# iognd.net
KiCad netlist of a schematic drawn in EAGLE
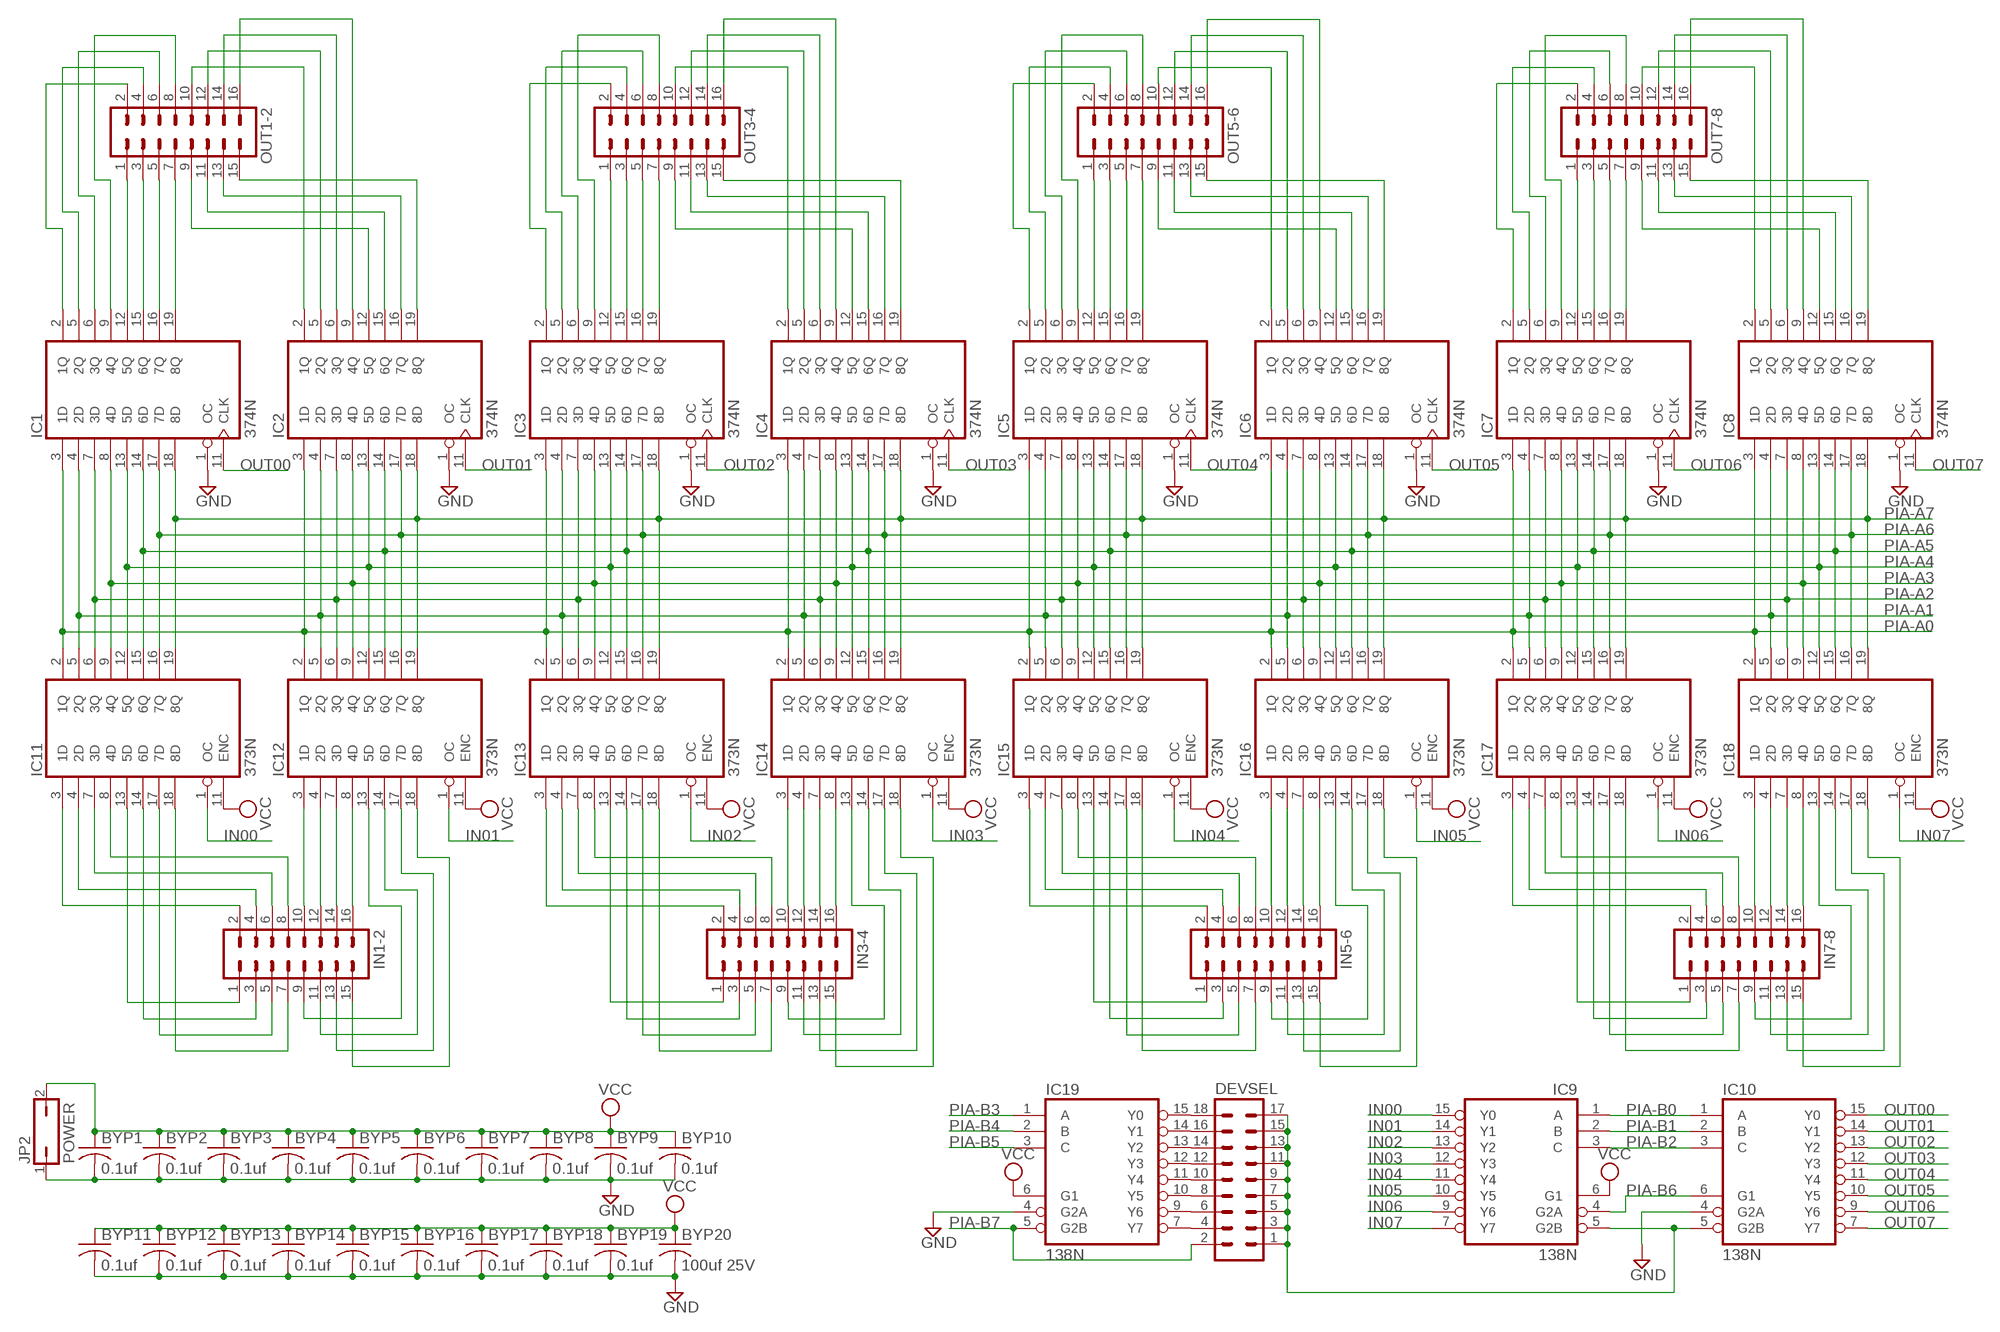
[diagram p0: schematic, sheet 1]
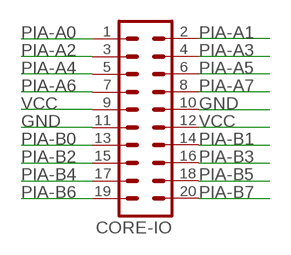
[diagram p1: schematic, sheet 2]

(export (version "E")
  (design (tool "Eeschema 10.0.6"))
  (components
    (comp (ref "CORE-IO")
      (value "MA10-2")
      (footprint "eagle-import:MA10-2")
      (libsource (lib "eagle-import") (part "MA10-2"))
    )
    (comp (ref "BYP1")
      (value "0.1uf")
      (footprint "eagle-import:C050-025X075")
      (libsource (lib "eagle-import") (part "C-US050-025X075"))
    )
    (comp (ref "BYP2")
      (value "0.1uf")
      (footprint "eagle-import:C050-025X075")
      (libsource (lib "eagle-import") (part "C-US050-025X075"))
    )
    (comp (ref "BYP3")
      (value "0.1uf")
      (footprint "eagle-import:C050-025X075")
      (libsource (lib "eagle-import") (part "C-US050-025X075"))
    )
    (comp (ref "BYP4")
      (value "0.1uf")
      (footprint "eagle-import:C050-025X075")
      (libsource (lib "eagle-import") (part "C-US050-025X075"))
    )
    (comp (ref "BYP5")
      (value "0.1uf")
      (footprint "eagle-import:C050-025X075")
      (libsource (lib "eagle-import") (part "C-US050-025X075"))
    )
    (comp (ref "BYP6")
      (value "0.1uf")
      (footprint "eagle-import:C050-025X075")
      (libsource (lib "eagle-import") (part "C-US050-025X075"))
    )
    (comp (ref "BYP7")
      (value "0.1uf")
      (footprint "eagle-import:C050-025X075")
      (libsource (lib "eagle-import") (part "C-US050-025X075"))
    )
    (comp (ref "BYP8")
      (value "0.1uf")
      (footprint "eagle-import:C050-025X075")
      (libsource (lib "eagle-import") (part "C-US050-025X075"))
    )
    (comp (ref "BYP9")
      (value "0.1uf")
      (footprint "eagle-import:C050-025X075")
      (libsource (lib "eagle-import") (part "C-US050-025X075"))
    )
    (comp (ref "BYP10")
      (value "0.1uf")
      (footprint "eagle-import:C050-025X075")
      (libsource (lib "eagle-import") (part "C-US050-025X075"))
    )
    (comp (ref "BYP11")
      (value "0.1uf")
      (footprint "eagle-import:C050-025X075")
      (libsource (lib "eagle-import") (part "C-US050-025X075"))
    )
    (comp (ref "BYP12")
      (value "0.1uf")
      (footprint "eagle-import:C050-025X075")
      (libsource (lib "eagle-import") (part "C-US050-025X075"))
    )
    (comp (ref "BYP13")
      (value "0.1uf")
      (footprint "eagle-import:C050-025X075")
      (libsource (lib "eagle-import") (part "C-US050-025X075"))
    )
    (comp (ref "BYP14")
      (value "0.1uf")
      (footprint "eagle-import:C050-025X075")
      (libsource (lib "eagle-import") (part "C-US050-025X075"))
    )
    (comp (ref "BYP15")
      (value "0.1uf")
      (footprint "eagle-import:C050-025X075")
      (libsource (lib "eagle-import") (part "C-US050-025X075"))
    )
    (comp (ref "BYP16")
      (value "0.1uf")
      (footprint "eagle-import:C050-025X075")
      (libsource (lib "eagle-import") (part "C-US050-025X075"))
    )
    (comp (ref "BYP17")
      (value "0.1uf")
      (footprint "eagle-import:C050-025X075")
      (libsource (lib "eagle-import") (part "C-US050-025X075"))
    )
    (comp (ref "BYP18")
      (value "0.1uf")
      (footprint "eagle-import:C050-025X075")
      (libsource (lib "eagle-import") (part "C-US050-025X075"))
    )
    (comp (ref "BYP19")
      (value "0.1uf")
      (footprint "eagle-import:C050-025X075")
      (libsource (lib "eagle-import") (part "C-US050-025X075"))
    )
    (comp (ref "BYP20")
      (value "100uf 25V")
      (footprint "eagle-import:C150-064X183")
      (libsource (lib "eagle-import") (part "C-US150-064X183"))
    )
    (comp (ref "DEVSEL")
      (value "MA09-2")
      (footprint "eagle-import:MA09-2")
      (libsource (lib "eagle-import") (part "MA09-2"))
    )
    (comp (ref "IC1")
      (value "374N")
      (footprint "eagle-import:DIL20")
      (libsource (lib "eagle-import") (part "74374NLS"))
    )
    (comp (ref "IC2")
      (value "374N")
      (footprint "eagle-import:DIL20")
      (libsource (lib "eagle-import") (part "74374NLS"))
    )
    (comp (ref "IC3")
      (value "374N")
      (footprint "eagle-import:DIL20")
      (libsource (lib "eagle-import") (part "74374NLS"))
    )
    (comp (ref "IC4")
      (value "374N")
      (footprint "eagle-import:DIL20")
      (libsource (lib "eagle-import") (part "74374NLS"))
    )
    (comp (ref "IC5")
      (value "374N")
      (footprint "eagle-import:DIL20")
      (libsource (lib "eagle-import") (part "74374NLS"))
    )
    (comp (ref "IC6")
      (value "374N")
      (footprint "eagle-import:DIL20")
      (libsource (lib "eagle-import") (part "74374NLS"))
    )
    (comp (ref "IC7")
      (value "374N")
      (footprint "eagle-import:DIL20")
      (libsource (lib "eagle-import") (part "74374NLS"))
    )
    (comp (ref "IC8")
      (value "374N")
      (footprint "eagle-import:DIL20")
      (libsource (lib "eagle-import") (part "74374NLS"))
    )
    (comp (ref "IC9")
      (value "138N")
      (footprint "eagle-import:DIL16")
      (libsource (lib "eagle-import") (part "74138NLS"))
    )
    (comp (ref "IC10")
      (value "138N")
      (footprint "eagle-import:DIL16")
      (libsource (lib "eagle-import") (part "74138NLS"))
    )
    (comp (ref "IC11")
      (value "373N")
      (footprint "eagle-import:DIL20")
      (libsource (lib "eagle-import") (part "74373NLS"))
    )
    (comp (ref "IC12")
      (value "373N")
      (footprint "eagle-import:DIL20")
      (libsource (lib "eagle-import") (part "74373NLS"))
    )
    (comp (ref "IC13")
      (value "373N")
      (footprint "eagle-import:DIL20")
      (libsource (lib "eagle-import") (part "74373NLS"))
    )
    (comp (ref "IC14")
      (value "373N")
      (footprint "eagle-import:DIL20")
      (libsource (lib "eagle-import") (part "74373NLS"))
    )
    (comp (ref "IC15")
      (value "373N")
      (footprint "eagle-import:DIL20")
      (libsource (lib "eagle-import") (part "74373NLS"))
    )
    (comp (ref "IC16")
      (value "373N")
      (footprint "eagle-import:DIL20")
      (libsource (lib "eagle-import") (part "74373NLS"))
    )
    (comp (ref "IC17")
      (value "373N")
      (footprint "eagle-import:DIL20")
      (libsource (lib "eagle-import") (part "74373NLS"))
    )
    (comp (ref "IC18")
      (value "373N")
      (footprint "eagle-import:DIL20")
      (libsource (lib "eagle-import") (part "74373NLS"))
    )
    (comp (ref "IC19")
      (value "138N")
      (footprint "eagle-import:DIL16")
      (libsource (lib "eagle-import") (part "74138NLS"))
    )
    (comp (ref "IN1-2")
      (value "MA08-2")
      (footprint "eagle-import:MA08-2")
      (libsource (lib "eagle-import") (part "MA08-2"))
    )
    (comp (ref "IN3-4")
      (value "MA08-2")
      (footprint "eagle-import:MA08-2")
      (libsource (lib "eagle-import") (part "MA08-2"))
    )
    (comp (ref "IN5-6")
      (value "MA08-2")
      (footprint "eagle-import:MA08-2")
      (libsource (lib "eagle-import") (part "MA08-2"))
    )
    (comp (ref "IN7-8")
      (value "MA08-2")
      (footprint "eagle-import:MA08-2")
      (libsource (lib "eagle-import") (part "MA08-2"))
    )
    (comp (ref "JP2")
      (value "POWER")
      (footprint "eagle-import:JP1")
      (libsource (lib "eagle-import") (part "JP1Q"))
    )
    (comp (ref "OUT1-2")
      (value "MA08-2")
      (footprint "eagle-import:MA08-2")
      (libsource (lib "eagle-import") (part "MA08-2"))
    )
    (comp (ref "OUT3-4")
      (value "MA08-2")
      (footprint "eagle-import:MA08-2")
      (libsource (lib "eagle-import") (part "MA08-2"))
    )
    (comp (ref "OUT5-6")
      (value "MA08-2")
      (footprint "eagle-import:MA08-2")
      (libsource (lib "eagle-import") (part "MA08-2"))
    )
    (comp (ref "OUT7-8")
      (value "MA08-2")
      (footprint "eagle-import:MA08-2")
      (libsource (lib "eagle-import") (part "MA08-2"))
    )
  )
  (nets
    (net (code "1") (name "GND") (class "Default")
      (node (ref "BYP1") (pin "2") (pinfunction "2_2") (pintype "passive"))
      (node (ref "BYP10") (pin "2") (pinfunction "2_2") (pintype "passive"))
      (node (ref "BYP11") (pin "2") (pinfunction "2_2") (pintype "passive"))
      (node (ref "BYP12") (pin "2") (pinfunction "2_2") (pintype "passive"))
      (node (ref "BYP13") (pin "2") (pinfunction "2_2") (pintype "passive"))
      (node (ref "BYP14") (pin "2") (pinfunction "2_2") (pintype "passive"))
      (node (ref "BYP15") (pin "2") (pinfunction "2_2") (pintype "passive"))
      (node (ref "BYP16") (pin "2") (pinfunction "2_2") (pintype "passive"))
      (node (ref "BYP17") (pin "2") (pinfunction "2_2") (pintype "passive"))
      (node (ref "BYP18") (pin "2") (pinfunction "2_2") (pintype "passive"))
      (node (ref "BYP19") (pin "2") (pinfunction "2_2") (pintype "passive"))
      (node (ref "BYP2") (pin "2") (pinfunction "2_2") (pintype "passive"))
      (node (ref "BYP20") (pin "2") (pinfunction "2_2") (pintype "passive"))
      (node (ref "BYP3") (pin "2") (pinfunction "2_2") (pintype "passive"))
      (node (ref "BYP4") (pin "2") (pinfunction "2_2") (pintype "passive"))
      (node (ref "BYP5") (pin "2") (pinfunction "2_2") (pintype "passive"))
      (node (ref "BYP6") (pin "2") (pinfunction "2_2") (pintype "passive"))
      (node (ref "BYP7") (pin "2") (pinfunction "2_2") (pintype "passive"))
      (node (ref "BYP8") (pin "2") (pinfunction "2_2") (pintype "passive"))
      (node (ref "BYP9") (pin "2") (pinfunction "2_2") (pintype "passive"))
      (node (ref "CORE-IO") (pin "10") (pinfunction "10_10") (pintype "passive"))
      (node (ref "CORE-IO") (pin "11") (pinfunction "11_11") (pintype "passive"))
      (node (ref "IC1") (pin "1") (pinfunction "OC_1") (pintype "input"))
      (node (ref "IC10") (pin "4") (pinfunction "G2A_4") (pintype "input"))
      (node (ref "IC19") (pin "4") (pinfunction "G2A_4") (pintype "input"))
      (node (ref "IC2") (pin "1") (pinfunction "OC_1") (pintype "input"))
      (node (ref "IC3") (pin "1") (pinfunction "OC_1") (pintype "input"))
      (node (ref "IC4") (pin "1") (pinfunction "OC_1") (pintype "input"))
      (node (ref "IC5") (pin "1") (pinfunction "OC_1") (pintype "input"))
      (node (ref "IC6") (pin "1") (pinfunction "OC_1") (pintype "input"))
      (node (ref "IC7") (pin "1") (pinfunction "OC_1") (pintype "input"))
      (node (ref "IC8") (pin "1") (pinfunction "OC_1") (pintype "input"))
      (node (ref "JP2") (pin "1") (pinfunction "1_1") (pintype "passive"))
    )
    (net (code "2") (name "IN00") (class "Default")
      (node (ref "IC11") (pin "1") (pinfunction "OC_1") (pintype "input"))
      (node (ref "IC9") (pin "15") (pinfunction "Y0_15") (pintype "output"))
    )
    (net (code "3") (name "IN01") (class "Default")
      (node (ref "IC12") (pin "1") (pinfunction "OC_1") (pintype "input"))
      (node (ref "IC9") (pin "14") (pinfunction "Y1_14") (pintype "output"))
    )
    (net (code "4") (name "IN02") (class "Default")
      (node (ref "IC13") (pin "1") (pinfunction "OC_1") (pintype "input"))
      (node (ref "IC9") (pin "13") (pinfunction "Y2_13") (pintype "output"))
    )
    (net (code "5") (name "IN03") (class "Default")
      (node (ref "IC14") (pin "1") (pinfunction "OC_1") (pintype "input"))
      (node (ref "IC9") (pin "12") (pinfunction "Y3_12") (pintype "output"))
    )
    (net (code "6") (name "IN04") (class "Default")
      (node (ref "IC15") (pin "1") (pinfunction "OC_1") (pintype "input"))
      (node (ref "IC9") (pin "11") (pinfunction "Y4_11") (pintype "output"))
    )
    (net (code "7") (name "IN05") (class "Default")
      (node (ref "IC16") (pin "1") (pinfunction "OC_1") (pintype "input"))
      (node (ref "IC9") (pin "10") (pinfunction "Y5_10") (pintype "output"))
    )
    (net (code "8") (name "IN06") (class "Default")
      (node (ref "IC17") (pin "1") (pinfunction "OC_1") (pintype "input"))
      (node (ref "IC9") (pin "9") (pinfunction "Y6_9") (pintype "output"))
    )
    (net (code "9") (name "IN07") (class "Default")
      (node (ref "IC18") (pin "1") (pinfunction "OC_1") (pintype "input"))
      (node (ref "IC9") (pin "7") (pinfunction "Y7_7") (pintype "output"))
    )
    (net (code "10") (name "Net-(IC1A-1Q)") (class "Default")
      (node (ref "IC1") (pin "2") (pinfunction "1Q_2") (pintype "tri_state"))
      (node (ref "OUT1-2") (pin "2") (pinfunction "2_2") (pintype "passive"))
    )
    (net (code "11") (name "Net-(IC1A-2Q)") (class "Default")
      (node (ref "IC1") (pin "5") (pinfunction "2Q_5") (pintype "tri_state"))
      (node (ref "OUT1-2") (pin "4") (pinfunction "4_4") (pintype "passive"))
    )
    (net (code "12") (name "Net-(IC1A-3Q)") (class "Default")
      (node (ref "IC1") (pin "6") (pinfunction "3Q_6") (pintype "tri_state"))
      (node (ref "OUT1-2") (pin "6") (pinfunction "6_6") (pintype "passive"))
    )
    (net (code "13") (name "Net-(IC1A-4Q)") (class "Default")
      (node (ref "IC1") (pin "9") (pinfunction "4Q_9") (pintype "tri_state"))
      (node (ref "OUT1-2") (pin "8") (pinfunction "8_8") (pintype "passive"))
    )
    (net (code "14") (name "Net-(IC1A-5Q)") (class "Default")
      (node (ref "IC1") (pin "12") (pinfunction "5Q_12") (pintype "tri_state"))
      (node (ref "OUT1-2") (pin "1") (pinfunction "1_1") (pintype "passive"))
    )
    (net (code "15") (name "Net-(IC1A-6Q)") (class "Default")
      (node (ref "IC1") (pin "15") (pinfunction "6Q_15") (pintype "tri_state"))
      (node (ref "OUT1-2") (pin "3") (pinfunction "3_3") (pintype "passive"))
    )
    (net (code "16") (name "Net-(IC1A-7Q)") (class "Default")
      (node (ref "IC1") (pin "16") (pinfunction "7Q_16") (pintype "tri_state"))
      (node (ref "OUT1-2") (pin "5") (pinfunction "5_5") (pintype "passive"))
    )
    (net (code "17") (name "Net-(IC1A-8Q)") (class "Default")
      (node (ref "IC1") (pin "19") (pinfunction "8Q_19") (pintype "tri_state"))
      (node (ref "OUT1-2") (pin "7") (pinfunction "7_7") (pintype "passive"))
    )
    (net (code "18") (name "Net-(IC2A-1Q)") (class "Default")
      (node (ref "IC2") (pin "2") (pinfunction "1Q_2") (pintype "tri_state"))
      (node (ref "OUT1-2") (pin "10") (pinfunction "10_10") (pintype "passive"))
    )
    (net (code "19") (name "Net-(IC2A-2Q)") (class "Default")
      (node (ref "IC2") (pin "5") (pinfunction "2Q_5") (pintype "tri_state"))
      (node (ref "OUT1-2") (pin "12") (pinfunction "12_12") (pintype "passive"))
    )
    (net (code "20") (name "Net-(IC2A-3Q)") (class "Default")
      (node (ref "IC2") (pin "6") (pinfunction "3Q_6") (pintype "tri_state"))
      (node (ref "OUT1-2") (pin "14") (pinfunction "14_14") (pintype "passive"))
    )
    (net (code "21") (name "Net-(IC2A-4Q)") (class "Default")
      (node (ref "IC2") (pin "9") (pinfunction "4Q_9") (pintype "tri_state"))
      (node (ref "OUT1-2") (pin "16") (pinfunction "16_16") (pintype "passive"))
    )
    (net (code "22") (name "Net-(IC2A-5Q)") (class "Default")
      (node (ref "IC2") (pin "12") (pinfunction "5Q_12") (pintype "tri_state"))
      (node (ref "OUT1-2") (pin "9") (pinfunction "9_9") (pintype "passive"))
    )
    (net (code "23") (name "Net-(IC2A-6Q)") (class "Default")
      (node (ref "IC2") (pin "15") (pinfunction "6Q_15") (pintype "tri_state"))
      (node (ref "OUT1-2") (pin "11") (pinfunction "11_11") (pintype "passive"))
    )
    (net (code "24") (name "Net-(IC2A-7Q)") (class "Default")
      (node (ref "IC2") (pin "16") (pinfunction "7Q_16") (pintype "tri_state"))
      (node (ref "OUT1-2") (pin "13") (pinfunction "13_13") (pintype "passive"))
    )
    (net (code "25") (name "Net-(IC2A-8Q)") (class "Default")
      (node (ref "IC2") (pin "19") (pinfunction "8Q_19") (pintype "tri_state"))
      (node (ref "OUT1-2") (pin "15") (pinfunction "15_15") (pintype "passive"))
    )
    (net (code "26") (name "Net-(IC3A-1Q)") (class "Default")
      (node (ref "IC3") (pin "2") (pinfunction "1Q_2") (pintype "tri_state"))
      (node (ref "OUT3-4") (pin "2") (pinfunction "2_2") (pintype "passive"))
    )
    (net (code "27") (name "Net-(IC3A-2Q)") (class "Default")
      (node (ref "IC3") (pin "5") (pinfunction "2Q_5") (pintype "tri_state"))
      (node (ref "OUT3-4") (pin "4") (pinfunction "4_4") (pintype "passive"))
    )
    (net (code "28") (name "Net-(IC3A-3Q)") (class "Default")
      (node (ref "IC3") (pin "6") (pinfunction "3Q_6") (pintype "tri_state"))
      (node (ref "OUT3-4") (pin "6") (pinfunction "6_6") (pintype "passive"))
    )
    (net (code "29") (name "Net-(IC3A-4Q)") (class "Default")
      (node (ref "IC3") (pin "9") (pinfunction "4Q_9") (pintype "tri_state"))
      (node (ref "OUT3-4") (pin "8") (pinfunction "8_8") (pintype "passive"))
    )
    (net (code "30") (name "Net-(IC3A-5Q)") (class "Default")
      (node (ref "IC3") (pin "12") (pinfunction "5Q_12") (pintype "tri_state"))
      (node (ref "OUT3-4") (pin "1") (pinfunction "1_1") (pintype "passive"))
    )
    (net (code "31") (name "Net-(IC3A-6Q)") (class "Default")
      (node (ref "IC3") (pin "15") (pinfunction "6Q_15") (pintype "tri_state"))
      (node (ref "OUT3-4") (pin "3") (pinfunction "3_3") (pintype "passive"))
    )
    (net (code "32") (name "Net-(IC3A-7Q)") (class "Default")
      (node (ref "IC3") (pin "16") (pinfunction "7Q_16") (pintype "tri_state"))
      (node (ref "OUT3-4") (pin "5") (pinfunction "5_5") (pintype "passive"))
    )
    (net (code "33") (name "Net-(IC3A-8Q)") (class "Default")
      (node (ref "IC3") (pin "19") (pinfunction "8Q_19") (pintype "tri_state"))
      (node (ref "OUT3-4") (pin "7") (pinfunction "7_7") (pintype "passive"))
    )
    (net (code "34") (name "Net-(IC4A-1Q)") (class "Default")
      (node (ref "IC4") (pin "2") (pinfunction "1Q_2") (pintype "tri_state"))
      (node (ref "OUT3-4") (pin "10") (pinfunction "10_10") (pintype "passive"))
    )
    (net (code "35") (name "Net-(IC4A-2Q)") (class "Default")
      (node (ref "IC4") (pin "5") (pinfunction "2Q_5") (pintype "tri_state"))
      (node (ref "OUT3-4") (pin "12") (pinfunction "12_12") (pintype "passive"))
    )
    (net (code "36") (name "Net-(IC4A-3Q)") (class "Default")
      (node (ref "IC4") (pin "6") (pinfunction "3Q_6") (pintype "tri_state"))
      (node (ref "OUT3-4") (pin "14") (pinfunction "14_14") (pintype "passive"))
    )
    (net (code "37") (name "Net-(IC4A-4Q)") (class "Default")
      (node (ref "IC4") (pin "9") (pinfunction "4Q_9") (pintype "tri_state"))
      (node (ref "OUT3-4") (pin "16") (pinfunction "16_16") (pintype "passive"))
    )
    (net (code "38") (name "Net-(IC4A-5Q)") (class "Default")
      (node (ref "IC4") (pin "12") (pinfunction "5Q_12") (pintype "tri_state"))
      (node (ref "OUT3-4") (pin "9") (pinfunction "9_9") (pintype "passive"))
    )
    (net (code "39") (name "Net-(IC4A-6Q)") (class "Default")
      (node (ref "IC4") (pin "15") (pinfunction "6Q_15") (pintype "tri_state"))
      (node (ref "OUT3-4") (pin "11") (pinfunction "11_11") (pintype "passive"))
    )
    (net (code "40") (name "Net-(IC4A-7Q)") (class "Default")
      (node (ref "IC4") (pin "16") (pinfunction "7Q_16") (pintype "tri_state"))
      (node (ref "OUT3-4") (pin "13") (pinfunction "13_13") (pintype "passive"))
    )
    (net (code "41") (name "Net-(IC4A-8Q)") (class "Default")
      (node (ref "IC4") (pin "19") (pinfunction "8Q_19") (pintype "tri_state"))
      (node (ref "OUT3-4") (pin "15") (pinfunction "15_15") (pintype "passive"))
    )
    (net (code "42") (name "Net-(IC5A-1Q)") (class "Default")
      (node (ref "IC5") (pin "2") (pinfunction "1Q_2") (pintype "tri_state"))
      (node (ref "OUT5-6") (pin "2") (pinfunction "2_2") (pintype "passive"))
    )
    (net (code "43") (name "Net-(IC5A-2Q)") (class "Default")
      (node (ref "IC5") (pin "5") (pinfunction "2Q_5") (pintype "tri_state"))
      (node (ref "OUT5-6") (pin "4") (pinfunction "4_4") (pintype "passive"))
    )
    (net (code "44") (name "Net-(IC5A-3Q)") (class "Default")
      (node (ref "IC5") (pin "6") (pinfunction "3Q_6") (pintype "tri_state"))
      (node (ref "OUT5-6") (pin "6") (pinfunction "6_6") (pintype "passive"))
    )
    (net (code "45") (name "Net-(IC5A-4Q)") (class "Default")
      (node (ref "IC5") (pin "9") (pinfunction "4Q_9") (pintype "tri_state"))
      (node (ref "OUT5-6") (pin "8") (pinfunction "8_8") (pintype "passive"))
    )
    (net (code "46") (name "Net-(IC5A-5Q)") (class "Default")
      (node (ref "IC5") (pin "12") (pinfunction "5Q_12") (pintype "tri_state"))
      (node (ref "OUT5-6") (pin "1") (pinfunction "1_1") (pintype "passive"))
    )
    (net (code "47") (name "Net-(IC5A-6Q)") (class "Default")
      (node (ref "IC5") (pin "15") (pinfunction "6Q_15") (pintype "tri_state"))
      (node (ref "OUT5-6") (pin "3") (pinfunction "3_3") (pintype "passive"))
    )
    (net (code "48") (name "Net-(IC5A-7Q)") (class "Default")
      (node (ref "IC5") (pin "16") (pinfunction "7Q_16") (pintype "tri_state"))
      (node (ref "OUT5-6") (pin "5") (pinfunction "5_5") (pintype "passive"))
    )
    (net (code "49") (name "Net-(IC5A-8Q)") (class "Default")
      (node (ref "IC5") (pin "19") (pinfunction "8Q_19") (pintype "tri_state"))
      (node (ref "OUT5-6") (pin "7") (pinfunction "7_7") (pintype "passive"))
    )
    (net (code "50") (name "Net-(IC6A-1Q)") (class "Default")
      (node (ref "IC6") (pin "2") (pinfunction "1Q_2") (pintype "tri_state"))
      (node (ref "OUT5-6") (pin "10") (pinfunction "10_10") (pintype "passive"))
    )
    (net (code "51") (name "Net-(IC6A-2Q)") (class "Default")
      (node (ref "IC6") (pin "5") (pinfunction "2Q_5") (pintype "tri_state"))
      (node (ref "OUT5-6") (pin "12") (pinfunction "12_12") (pintype "passive"))
    )
    (net (code "52") (name "Net-(IC6A-3Q)") (class "Default")
      (node (ref "IC6") (pin "6") (pinfunction "3Q_6") (pintype "tri_state"))
      (node (ref "OUT5-6") (pin "14") (pinfunction "14_14") (pintype "passive"))
    )
    (net (code "53") (name "Net-(IC6A-4Q)") (class "Default")
      (node (ref "IC6") (pin "9") (pinfunction "4Q_9") (pintype "tri_state"))
      (node (ref "OUT5-6") (pin "16") (pinfunction "16_16") (pintype "passive"))
    )
    (net (code "54") (name "Net-(IC6A-5Q)") (class "Default")
      (node (ref "IC6") (pin "12") (pinfunction "5Q_12") (pintype "tri_state"))
      (node (ref "OUT5-6") (pin "9") (pinfunction "9_9") (pintype "passive"))
    )
    (net (code "55") (name "Net-(IC6A-6Q)") (class "Default")
      (node (ref "IC6") (pin "15") (pinfunction "6Q_15") (pintype "tri_state"))
      (node (ref "OUT5-6") (pin "11") (pinfunction "11_11") (pintype "passive"))
    )
    (net (code "56") (name "Net-(IC6A-7Q)") (class "Default")
      (node (ref "IC6") (pin "16") (pinfunction "7Q_16") (pintype "tri_state"))
      (node (ref "OUT5-6") (pin "13") (pinfunction "13_13") (pintype "passive"))
    )
    (net (code "57") (name "Net-(IC6A-8Q)") (class "Default")
      (node (ref "IC6") (pin "19") (pinfunction "8Q_19") (pintype "tri_state"))
      (node (ref "OUT5-6") (pin "15") (pinfunction "15_15") (pintype "passive"))
    )
    (net (code "58") (name "Net-(IC7A-1Q)") (class "Default")
      (node (ref "IC7") (pin "2") (pinfunction "1Q_2") (pintype "tri_state"))
      (node (ref "OUT7-8") (pin "2") (pinfunction "2_2") (pintype "passive"))
    )
    (net (code "59") (name "Net-(IC7A-2Q)") (class "Default")
      (node (ref "IC7") (pin "5") (pinfunction "2Q_5") (pintype "tri_state"))
      (node (ref "OUT7-8") (pin "4") (pinfunction "4_4") (pintype "passive"))
    )
    (net (code "60") (name "Net-(IC7A-3Q)") (class "Default")
      (node (ref "IC7") (pin "6") (pinfunction "3Q_6") (pintype "tri_state"))
      (node (ref "OUT7-8") (pin "6") (pinfunction "6_6") (pintype "passive"))
    )
    (net (code "61") (name "Net-(IC7A-4Q)") (class "Default")
      (node (ref "IC7") (pin "9") (pinfunction "4Q_9") (pintype "tri_state"))
      (node (ref "OUT7-8") (pin "8") (pinfunction "8_8") (pintype "passive"))
    )
    (net (code "62") (name "Net-(IC7A-5Q)") (class "Default")
      (node (ref "IC7") (pin "12") (pinfunction "5Q_12") (pintype "tri_state"))
      (node (ref "OUT7-8") (pin "1") (pinfunction "1_1") (pintype "passive"))
    )
    (net (code "63") (name "Net-(IC7A-6Q)") (class "Default")
      (node (ref "IC7") (pin "15") (pinfunction "6Q_15") (pintype "tri_state"))
      (node (ref "OUT7-8") (pin "3") (pinfunction "3_3") (pintype "passive"))
    )
    (net (code "64") (name "Net-(IC7A-7Q)") (class "Default")
      (node (ref "IC7") (pin "16") (pinfunction "7Q_16") (pintype "tri_state"))
      (node (ref "OUT7-8") (pin "5") (pinfunction "5_5") (pintype "passive"))
    )
    (net (code "65") (name "Net-(IC7A-8Q)") (class "Default")
      (node (ref "IC7") (pin "19") (pinfunction "8Q_19") (pintype "tri_state"))
      (node (ref "OUT7-8") (pin "7") (pinfunction "7_7") (pintype "passive"))
    )
    (net (code "66") (name "Net-(IC8A-1Q)") (class "Default")
      (node (ref "IC8") (pin "2") (pinfunction "1Q_2") (pintype "tri_state"))
      (node (ref "OUT7-8") (pin "10") (pinfunction "10_10") (pintype "passive"))
    )
    (net (code "67") (name "Net-(IC8A-2Q)") (class "Default")
      (node (ref "IC8") (pin "5") (pinfunction "2Q_5") (pintype "tri_state"))
      (node (ref "OUT7-8") (pin "12") (pinfunction "12_12") (pintype "passive"))
    )
    (net (code "68") (name "Net-(IC8A-3Q)") (class "Default")
      (node (ref "IC8") (pin "6") (pinfunction "3Q_6") (pintype "tri_state"))
      (node (ref "OUT7-8") (pin "14") (pinfunction "14_14") (pintype "passive"))
    )
    (net (code "69") (name "Net-(IC8A-4Q)") (class "Default")
      (node (ref "IC8") (pin "9") (pinfunction "4Q_9") (pintype "tri_state"))
      (node (ref "OUT7-8") (pin "16") (pinfunction "16_16") (pintype "passive"))
    )
    (net (code "70") (name "Net-(IC8A-5Q)") (class "Default")
      (node (ref "IC8") (pin "12") (pinfunction "5Q_12") (pintype "tri_state"))
      (node (ref "OUT7-8") (pin "9") (pinfunction "9_9") (pintype "passive"))
    )
    (net (code "71") (name "Net-(IC8A-6Q)") (class "Default")
      (node (ref "IC8") (pin "15") (pinfunction "6Q_15") (pintype "tri_state"))
      (node (ref "OUT7-8") (pin "11") (pinfunction "11_11") (pintype "passive"))
    )
    (net (code "72") (name "Net-(IC8A-7Q)") (class "Default")
      (node (ref "IC8") (pin "16") (pinfunction "7Q_16") (pintype "tri_state"))
      (node (ref "OUT7-8") (pin "13") (pinfunction "13_13") (pintype "passive"))
    )
    (net (code "73") (name "Net-(IC8A-8Q)") (class "Default")
      (node (ref "IC8") (pin "19") (pinfunction "8Q_19") (pintype "tri_state"))
      (node (ref "OUT7-8") (pin "15") (pinfunction "15_15") (pintype "passive"))
    )
    (net (code "74") (name "Net-(IC10A-G2B)") (class "Default")
      (node (ref "DEVSEL") (pin "1") (pinfunction "1_1") (pintype "passive"))
      (node (ref "DEVSEL") (pin "11") (pinfunction "11_11") (pintype "passive"))
      (node (ref "DEVSEL") (pin "13") (pinfunction "13_13") (pintype "passive"))
      (node (ref "DEVSEL") (pin "15") (pinfunction "15_15") (pintype "passive"))
      (node (ref "DEVSEL") (pin "17") (pinfunction "17_17") (pintype "passive"))
      (node (ref "DEVSEL") (pin "3") (pinfunction "3_3") (pintype "passive"))
      (node (ref "DEVSEL") (pin "5") (pinfunction "5_5") (pintype "passive"))
      (node (ref "DEVSEL") (pin "7") (pinfunction "7_7") (pintype "passive"))
      (node (ref "DEVSEL") (pin "9") (pinfunction "9_9") (pintype "passive"))
      (node (ref "IC10") (pin "5") (pinfunction "G2B_5") (pintype "input"))
      (node (ref "IC9") (pin "5") (pinfunction "G2B_5") (pintype "input"))
    )
    (net (code "75") (name "Net-(IC11A-1D)") (class "Default")
      (node (ref "IC11") (pin "3") (pinfunction "1D_3") (pintype "input"))
      (node (ref "IN1-2") (pin "2") (pinfunction "2_2") (pintype "passive"))
    )
    (net (code "76") (name "Net-(IC11A-2D)") (class "Default")
      (node (ref "IC11") (pin "4") (pinfunction "2D_4") (pintype "input"))
      (node (ref "IN1-2") (pin "4") (pinfunction "4_4") (pintype "passive"))
    )
    (net (code "77") (name "Net-(IC11A-3D)") (class "Default")
      (node (ref "IC11") (pin "7") (pinfunction "3D_7") (pintype "input"))
      (node (ref "IN1-2") (pin "6") (pinfunction "6_6") (pintype "passive"))
    )
    (net (code "78") (name "Net-(IC11A-4D)") (class "Default")
      (node (ref "IC11") (pin "8") (pinfunction "4D_8") (pintype "input"))
      (node (ref "IN1-2") (pin "8") (pinfunction "8_8") (pintype "passive"))
    )
    (net (code "79") (name "Net-(IC11A-5D)") (class "Default")
      (node (ref "IC11") (pin "13") (pinfunction "5D_13") (pintype "input"))
      (node (ref "IN1-2") (pin "1") (pinfunction "1_1") (pintype "passive"))
    )
    (net (code "80") (name "Net-(IC11A-6D)") (class "Default")
      (node (ref "IC11") (pin "14") (pinfunction "6D_14") (pintype "input"))
      (node (ref "IN1-2") (pin "3") (pinfunction "3_3") (pintype "passive"))
    )
    (net (code "81") (name "Net-(IC11A-7D)") (class "Default")
      (node (ref "IC11") (pin "17") (pinfunction "7D_17") (pintype "input"))
      (node (ref "IN1-2") (pin "5") (pinfunction "5_5") (pintype "passive"))
    )
    (net (code "82") (name "Net-(IC11A-8D)") (class "Default")
      (node (ref "IC11") (pin "18") (pinfunction "8D_18") (pintype "input"))
      (node (ref "IN1-2") (pin "7") (pinfunction "7_7") (pintype "passive"))
    )
    (net (code "83") (name "Net-(IC12A-1D)") (class "Default")
      (node (ref "IC12") (pin "3") (pinfunction "1D_3") (pintype "input"))
      (node (ref "IN1-2") (pin "10") (pinfunction "10_10") (pintype "passive"))
    )
    (net (code "84") (name "Net-(IC12A-2D)") (class "Default")
      (node (ref "IC12") (pin "4") (pinfunction "2D_4") (pintype "input"))
      (node (ref "IN1-2") (pin "12") (pinfunction "12_12") (pintype "passive"))
    )
    (net (code "85") (name "Net-(IC12A-3D)") (class "Default")
      (node (ref "IC12") (pin "7") (pinfunction "3D_7") (pintype "input"))
      (node (ref "IN1-2") (pin "14") (pinfunction "14_14") (pintype "passive"))
    )
    (net (code "86") (name "Net-(IC12A-4D)") (class "Default")
      (node (ref "IC12") (pin "8") (pinfunction "4D_8") (pintype "input"))
      (node (ref "IN1-2") (pin "16") (pinfunction "16_16") (pintype "passive"))
    )
    (net (code "87") (name "Net-(IC12A-5D)") (class "Default")
      (node (ref "IC12") (pin "13") (pinfunction "5D_13") (pintype "input"))
      (node (ref "IN1-2") (pin "9") (pinfunction "9_9") (pintype "passive"))
    )
    (net (code "88") (name "Net-(IC12A-6D)") (class "Default")
      (node (ref "IC12") (pin "14") (pinfunction "6D_14") (pintype "input"))
      (node (ref "IN1-2") (pin "11") (pinfunction "11_11") (pintype "passive"))
    )
    (net (code "89") (name "Net-(IC12A-7D)") (class "Default")
      (node (ref "IC12") (pin "17") (pinfunction "7D_17") (pintype "input"))
      (node (ref "IN1-2") (pin "13") (pinfunction "13_13") (pintype "passive"))
    )
    (net (code "90") (name "Net-(IC12A-8D)") (class "Default")
      (node (ref "IC12") (pin "18") (pinfunction "8D_18") (pintype "input"))
      (node (ref "IN1-2") (pin "15") (pinfunction "15_15") (pintype "passive"))
    )
    (net (code "91") (name "Net-(IC13A-1D)") (class "Default")
      (node (ref "IC13") (pin "3") (pinfunction "1D_3") (pintype "input"))
      (node (ref "IN3-4") (pin "2") (pinfunction "2_2") (pintype "passive"))
    )
    (net (code "92") (name "Net-(IC13A-2D)") (class "Default")
      (node (ref "IC13") (pin "4") (pinfunction "2D_4") (pintype "input"))
      (node (ref "IN3-4") (pin "4") (pinfunction "4_4") (pintype "passive"))
    )
    (net (code "93") (name "Net-(IC13A-3D)") (class "Default")
      (node (ref "IC13") (pin "7") (pinfunction "3D_7") (pintype "input"))
      (node (ref "IN3-4") (pin "6") (pinfunction "6_6") (pintype "passive"))
    )
    (net (code "94") (name "Net-(IC13A-4D)") (class "Default")
      (node (ref "IC13") (pin "8") (pinfunction "4D_8") (pintype "input"))
      (node (ref "IN3-4") (pin "8") (pinfunction "8_8") (pintype "passive"))
    )
    (net (code "95") (name "Net-(IC13A-5D)") (class "Default")
      (node (ref "IC13") (pin "13") (pinfunction "5D_13") (pintype "input"))
      (node (ref "IN3-4") (pin "1") (pinfunction "1_1") (pintype "passive"))
    )
    (net (code "96") (name "Net-(IC13A-6D)") (class "Default")
      (node (ref "IC13") (pin "14") (pinfunction "6D_14") (pintype "input"))
      (node (ref "IN3-4") (pin "3") (pinfunction "3_3") (pintype "passive"))
    )
    (net (code "97") (name "Net-(IC13A-7D)") (class "Default")
      (node (ref "IC13") (pin "17") (pinfunction "7D_17") (pintype "input"))
      (node (ref "IN3-4") (pin "5") (pinfunction "5_5") (pintype "passive"))
    )
    (net (code "98") (name "Net-(IC13A-8D)") (class "Default")
      (node (ref "IC13") (pin "18") (pinfunction "8D_18") (pintype "input"))
      (node (ref "IN3-4") (pin "7") (pinfunction "7_7") (pintype "passive"))
    )
    (net (code "99") (name "Net-(IC14A-1D)") (class "Default")
      (node (ref "IC14") (pin "3") (pinfunction "1D_3") (pintype "input"))
      (node (ref "IN3-4") (pin "10") (pinfunction "10_10") (pintype "passive"))
    )
    (net (code "100") (name "Net-(IC14A-2D)") (class "Default")
      (node (ref "IC14") (pin "4") (pinfunction "2D_4") (pintype "input"))
      (node (ref "IN3-4") (pin "12") (pinfunction "12_12") (pintype "passive"))
    )
    (net (code "101") (name "Net-(IC14A-3D)") (class "Default")
      (node (ref "IC14") (pin "7") (pinfunction "3D_7") (pintype "input"))
      (node (ref "IN3-4") (pin "14") (pinfunction "14_14") (pintype "passive"))
    )
    (net (code "102") (name "Net-(IC14A-4D)") (class "Default")
      (node (ref "IC14") (pin "8") (pinfunction "4D_8") (pintype "input"))
      (node (ref "IN3-4") (pin "16") (pinfunction "16_16") (pintype "passive"))
    )
    (net (code "103") (name "Net-(IC14A-5D)") (class "Default")
      (node (ref "IC14") (pin "13") (pinfunction "5D_13") (pintype "input"))
      (node (ref "IN3-4") (pin "9") (pinfunction "9_9") (pintype "passive"))
    )
    (net (code "104") (name "Net-(IC14A-6D)") (class "Default")
      (node (ref "IC14") (pin "14") (pinfunction "6D_14") (pintype "input"))
      (node (ref "IN3-4") (pin "11") (pinfunction "11_11") (pintype "passive"))
    )
    (net (code "105") (name "Net-(IC14A-7D)") (class "Default")
      (node (ref "IC14") (pin "17") (pinfunction "7D_17") (pintype "input"))
      (node (ref "IN3-4") (pin "13") (pinfunction "13_13") (pintype "passive"))
    )
    (net (code "106") (name "Net-(IC14A-8D)") (class "Default")
      (node (ref "IC14") (pin "18") (pinfunction "8D_18") (pintype "input"))
      (node (ref "IN3-4") (pin "15") (pinfunction "15_15") (pintype "passive"))
    )
    (net (code "107") (name "Net-(IC15A-1D)") (class "Default")
      (node (ref "IC15") (pin "3") (pinfunction "1D_3") (pintype "input"))
      (node (ref "IN5-6") (pin "2") (pinfunction "2_2") (pintype "passive"))
    )
    (net (code "108") (name "Net-(IC15A-2D)") (class "Default")
      (node (ref "IC15") (pin "4") (pinfunction "2D_4") (pintype "input"))
      (node (ref "IN5-6") (pin "4") (pinfunction "4_4") (pintype "passive"))
    )
    (net (code "109") (name "Net-(IC15A-3D)") (class "Default")
      (node (ref "IC15") (pin "7") (pinfunction "3D_7") (pintype "input"))
      (node (ref "IN5-6") (pin "6") (pinfunction "6_6") (pintype "passive"))
    )
    (net (code "110") (name "Net-(IC15A-4D)") (class "Default")
      (node (ref "IC15") (pin "8") (pinfunction "4D_8") (pintype "input"))
      (node (ref "IN5-6") (pin "8") (pinfunction "8_8") (pintype "passive"))
    )
    (net (code "111") (name "Net-(IC15A-5D)") (class "Default")
      (node (ref "IC15") (pin "13") (pinfunction "5D_13") (pintype "input"))
      (node (ref "IN5-6") (pin "1") (pinfunction "1_1") (pintype "passive"))
    )
    (net (code "112") (name "Net-(IC15A-6D)") (class "Default")
      (node (ref "IC15") (pin "14") (pinfunction "6D_14") (pintype "input"))
      (node (ref "IN5-6") (pin "3") (pinfunction "3_3") (pintype "passive"))
    )
    (net (code "113") (name "Net-(IC15A-7D)") (class "Default")
      (node (ref "IC15") (pin "17") (pinfunction "7D_17") (pintype "input"))
      (node (ref "IN5-6") (pin "5") (pinfunction "5_5") (pintype "passive"))
    )
    (net (code "114") (name "Net-(IC15A-8D)") (class "Default")
      (node (ref "IC15") (pin "18") (pinfunction "8D_18") (pintype "input"))
      (node (ref "IN5-6") (pin "7") (pinfunction "7_7") (pintype "passive"))
    )
    (net (code "115") (name "Net-(IC16A-1D)") (class "Default")
      (node (ref "IC16") (pin "3") (pinfunction "1D_3") (pintype "input"))
      (node (ref "IN5-6") (pin "10") (pinfunction "10_10") (pintype "passive"))
    )
    (net (code "116") (name "Net-(IC16A-2D)") (class "Default")
      (node (ref "IC16") (pin "4") (pinfunction "2D_4") (pintype "input"))
      (node (ref "IN5-6") (pin "12") (pinfunction "12_12") (pintype "passive"))
    )
    (net (code "117") (name "Net-(IC16A-3D)") (class "Default")
      (node (ref "IC16") (pin "7") (pinfunction "3D_7") (pintype "input"))
      (node (ref "IN5-6") (pin "14") (pinfunction "14_14") (pintype "passive"))
    )
    (net (code "118") (name "Net-(IC16A-4D)") (class "Default")
      (node (ref "IC16") (pin "8") (pinfunction "4D_8") (pintype "input"))
      (node (ref "IN5-6") (pin "16") (pinfunction "16_16") (pintype "passive"))
    )
    (net (code "119") (name "Net-(IC16A-5D)") (class "Default")
      (node (ref "IC16") (pin "13") (pinfunction "5D_13") (pintype "input"))
      (node (ref "IN5-6") (pin "9") (pinfunction "9_9") (pintype "passive"))
    )
    (net (code "120") (name "Net-(IC16A-6D)") (class "Default")
      (node (ref "IC16") (pin "14") (pinfunction "6D_14") (pintype "input"))
      (node (ref "IN5-6") (pin "11") (pinfunction "11_11") (pintype "passive"))
    )
    (net (code "121") (name "Net-(IC16A-7D)") (class "Default")
      (node (ref "IC16") (pin "17") (pinfunction "7D_17") (pintype "input"))
      (node (ref "IN5-6") (pin "13") (pinfunction "13_13") (pintype "passive"))
    )
    (net (code "122") (name "Net-(IC16A-8D)") (class "Default")
      (node (ref "IC16") (pin "18") (pinfunction "8D_18") (pintype "input"))
      (node (ref "IN5-6") (pin "15") (pinfunction "15_15") (pintype "passive"))
    )
    (net (code "123") (name "Net-(IC17A-1D)") (class "Default")
      (node (ref "IC17") (pin "3") (pinfunction "1D_3") (pintype "input"))
      (node (ref "IN7-8") (pin "2") (pinfunction "2_2") (pintype "passive"))
    )
    (net (code "124") (name "Net-(IC17A-2D)") (class "Default")
      (node (ref "IC17") (pin "4") (pinfunction "2D_4") (pintype "input"))
      (node (ref "IN7-8") (pin "4") (pinfunction "4_4") (pintype "passive"))
    )
    (net (code "125") (name "Net-(IC17A-3D)") (class "Default")
      (node (ref "IC17") (pin "7") (pinfunction "3D_7") (pintype "input"))
      (node (ref "IN7-8") (pin "6") (pinfunction "6_6") (pintype "passive"))
    )
    (net (code "126") (name "Net-(IC17A-4D)") (class "Default")
      (node (ref "IC17") (pin "8") (pinfunction "4D_8") (pintype "input"))
      (node (ref "IN7-8") (pin "8") (pinfunction "8_8") (pintype "passive"))
    )
    (net (code "127") (name "Net-(IC17A-5D)") (class "Default")
      (node (ref "IC17") (pin "13") (pinfunction "5D_13") (pintype "input"))
      (node (ref "IN7-8") (pin "1") (pinfunction "1_1") (pintype "passive"))
    )
    (net (code "128") (name "Net-(IC17A-6D)") (class "Default")
      (node (ref "IC17") (pin "14") (pinfunction "6D_14") (pintype "input"))
      (node (ref "IN7-8") (pin "3") (pinfunction "3_3") (pintype "passive"))
    )
    (net (code "129") (name "Net-(IC17A-7D)") (class "Default")
      (node (ref "IC17") (pin "17") (pinfunction "7D_17") (pintype "input"))
      (node (ref "IN7-8") (pin "5") (pinfunction "5_5") (pintype "passive"))
    )
    (net (code "130") (name "Net-(IC17A-8D)") (class "Default")
      (node (ref "IC17") (pin "18") (pinfunction "8D_18") (pintype "input"))
      (node (ref "IN7-8") (pin "7") (pinfunction "7_7") (pintype "passive"))
    )
    (net (code "131") (name "Net-(IC18A-1D)") (class "Default")
      (node (ref "IC18") (pin "3") (pinfunction "1D_3") (pintype "input"))
      (node (ref "IN7-8") (pin "10") (pinfunction "10_10") (pintype "passive"))
    )
    (net (code "132") (name "Net-(IC18A-2D)") (class "Default")
      (node (ref "IC18") (pin "4") (pinfunction "2D_4") (pintype "input"))
      (node (ref "IN7-8") (pin "12") (pinfunction "12_12") (pintype "passive"))
    )
    (net (code "133") (name "Net-(IC18A-3D)") (class "Default")
      (node (ref "IC18") (pin "7") (pinfunction "3D_7") (pintype "input"))
      (node (ref "IN7-8") (pin "14") (pinfunction "14_14") (pintype "passive"))
    )
    (net (code "134") (name "Net-(IC18A-4D)") (class "Default")
      (node (ref "IC18") (pin "8") (pinfunction "4D_8") (pintype "input"))
      (node (ref "IN7-8") (pin "16") (pinfunction "16_16") (pintype "passive"))
    )
    (net (code "135") (name "Net-(IC18A-5D)") (class "Default")
      (node (ref "IC18") (pin "13") (pinfunction "5D_13") (pintype "input"))
      (node (ref "IN7-8") (pin "9") (pinfunction "9_9") (pintype "passive"))
    )
    (net (code "136") (name "Net-(IC18A-6D)") (class "Default")
      (node (ref "IC18") (pin "14") (pinfunction "6D_14") (pintype "input"))
      (node (ref "IN7-8") (pin "11") (pinfunction "11_11") (pintype "passive"))
    )
    (net (code "137") (name "Net-(IC18A-7D)") (class "Default")
      (node (ref "IC18") (pin "17") (pinfunction "7D_17") (pintype "input"))
      (node (ref "IN7-8") (pin "13") (pinfunction "13_13") (pintype "passive"))
    )
    (net (code "138") (name "Net-(IC18A-8D)") (class "Default")
      (node (ref "IC18") (pin "18") (pinfunction "8D_18") (pintype "input"))
      (node (ref "IN7-8") (pin "15") (pinfunction "15_15") (pintype "passive"))
    )
    (net (code "139") (name "Net-(IC19A-Y0)") (class "Default")
      (node (ref "DEVSEL") (pin "18") (pinfunction "18_18") (pintype "passive"))
      (node (ref "IC19") (pin "15") (pinfunction "Y0_15") (pintype "output"))
    )
    (net (code "140") (name "Net-(IC19A-Y1)") (class "Default")
      (node (ref "DEVSEL") (pin "16") (pinfunction "16_16") (pintype "passive"))
      (node (ref "IC19") (pin "14") (pinfunction "Y1_14") (pintype "output"))
    )
    (net (code "141") (name "Net-(IC19A-Y2)") (class "Default")
      (node (ref "DEVSEL") (pin "14") (pinfunction "14_14") (pintype "passive"))
      (node (ref "IC19") (pin "13") (pinfunction "Y2_13") (pintype "output"))
    )
    (net (code "142") (name "Net-(IC19A-Y3)") (class "Default")
      (node (ref "DEVSEL") (pin "12") (pinfunction "12_12") (pintype "passive"))
      (node (ref "IC19") (pin "12") (pinfunction "Y3_12") (pintype "output"))
    )
    (net (code "143") (name "Net-(IC19A-Y4)") (class "Default")
      (node (ref "DEVSEL") (pin "10") (pinfunction "10_10") (pintype "passive"))
      (node (ref "IC19") (pin "11") (pinfunction "Y4_11") (pintype "output"))
    )
    (net (code "144") (name "Net-(IC19A-Y5)") (class "Default")
      (node (ref "DEVSEL") (pin "8") (pinfunction "8_8") (pintype "passive"))
      (node (ref "IC19") (pin "10") (pinfunction "Y5_10") (pintype "output"))
    )
    (net (code "145") (name "Net-(IC19A-Y6)") (class "Default")
      (node (ref "DEVSEL") (pin "6") (pinfunction "6_6") (pintype "passive"))
      (node (ref "IC19") (pin "9") (pinfunction "Y6_9") (pintype "output"))
    )
    (net (code "146") (name "Net-(IC19A-Y7)") (class "Default")
      (node (ref "DEVSEL") (pin "4") (pinfunction "4_4") (pintype "passive"))
      (node (ref "IC19") (pin "7") (pinfunction "Y7_7") (pintype "output"))
    )
    (net (code "147") (name "OUT00") (class "Default")
      (node (ref "IC1") (pin "11") (pinfunction "CLK_11") (pintype "input"))
      (node (ref "IC10") (pin "15") (pinfunction "Y0_15") (pintype "output"))
    )
    (net (code "148") (name "OUT01") (class "Default")
      (node (ref "IC10") (pin "14") (pinfunction "Y1_14") (pintype "output"))
      (node (ref "IC2") (pin "11") (pinfunction "CLK_11") (pintype "input"))
    )
    (net (code "149") (name "OUT02") (class "Default")
      (node (ref "IC10") (pin "13") (pinfunction "Y2_13") (pintype "output"))
      (node (ref "IC3") (pin "11") (pinfunction "CLK_11") (pintype "input"))
    )
    (net (code "150") (name "OUT03") (class "Default")
      (node (ref "IC10") (pin "12") (pinfunction "Y3_12") (pintype "output"))
      (node (ref "IC4") (pin "11") (pinfunction "CLK_11") (pintype "input"))
    )
    (net (code "151") (name "OUT04") (class "Default")
      (node (ref "IC10") (pin "11") (pinfunction "Y4_11") (pintype "output"))
      (node (ref "IC5") (pin "11") (pinfunction "CLK_11") (pintype "input"))
    )
    (net (code "152") (name "OUT05") (class "Default")
      (node (ref "IC10") (pin "10") (pinfunction "Y5_10") (pintype "output"))
      (node (ref "IC6") (pin "11") (pinfunction "CLK_11") (pintype "input"))
    )
    (net (code "153") (name "OUT06") (class "Default")
      (node (ref "IC10") (pin "9") (pinfunction "Y6_9") (pintype "output"))
      (node (ref "IC7") (pin "11") (pinfunction "CLK_11") (pintype "input"))
    )
    (net (code "154") (name "OUT07") (class "Default")
      (node (ref "IC10") (pin "7") (pinfunction "Y7_7") (pintype "output"))
      (node (ref "IC8") (pin "11") (pinfunction "CLK_11") (pintype "input"))
    )
    (net (code "155") (name "PIA-A0") (class "Default")
      (node (ref "CORE-IO") (pin "1") (pinfunction "1_1") (pintype "passive"))
      (node (ref "IC1") (pin "3") (pinfunction "1D_3") (pintype "input"))
      (node (ref "IC11") (pin "2") (pinfunction "1Q_2") (pintype "tri_state"))
      (node (ref "IC12") (pin "2") (pinfunction "1Q_2") (pintype "tri_state"))
      (node (ref "IC13") (pin "2") (pinfunction "1Q_2") (pintype "tri_state"))
      (node (ref "IC14") (pin "2") (pinfunction "1Q_2") (pintype "tri_state"))
      (node (ref "IC15") (pin "2") (pinfunction "1Q_2") (pintype "tri_state"))
      (node (ref "IC16") (pin "2") (pinfunction "1Q_2") (pintype "tri_state"))
      (node (ref "IC17") (pin "2") (pinfunction "1Q_2") (pintype "tri_state"))
      (node (ref "IC18") (pin "2") (pinfunction "1Q_2") (pintype "tri_state"))
      (node (ref "IC2") (pin "3") (pinfunction "1D_3") (pintype "input"))
      (node (ref "IC3") (pin "3") (pinfunction "1D_3") (pintype "input"))
      (node (ref "IC4") (pin "3") (pinfunction "1D_3") (pintype "input"))
      (node (ref "IC5") (pin "3") (pinfunction "1D_3") (pintype "input"))
      (node (ref "IC6") (pin "3") (pinfunction "1D_3") (pintype "input"))
      (node (ref "IC7") (pin "3") (pinfunction "1D_3") (pintype "input"))
      (node (ref "IC8") (pin "3") (pinfunction "1D_3") (pintype "input"))
    )
    (net (code "156") (name "PIA-A1") (class "Default")
      (node (ref "CORE-IO") (pin "2") (pinfunction "2_2") (pintype "passive"))
      (node (ref "IC1") (pin "4") (pinfunction "2D_4") (pintype "input"))
      (node (ref "IC11") (pin "5") (pinfunction "2Q_5") (pintype "tri_state"))
      (node (ref "IC12") (pin "5") (pinfunction "2Q_5") (pintype "tri_state"))
      (node (ref "IC13") (pin "5") (pinfunction "2Q_5") (pintype "tri_state"))
      (node (ref "IC14") (pin "5") (pinfunction "2Q_5") (pintype "tri_state"))
      (node (ref "IC15") (pin "5") (pinfunction "2Q_5") (pintype "tri_state"))
      (node (ref "IC16") (pin "5") (pinfunction "2Q_5") (pintype "tri_state"))
      (node (ref "IC17") (pin "5") (pinfunction "2Q_5") (pintype "tri_state"))
      (node (ref "IC18") (pin "5") (pinfunction "2Q_5") (pintype "tri_state"))
      (node (ref "IC2") (pin "4") (pinfunction "2D_4") (pintype "input"))
      (node (ref "IC3") (pin "4") (pinfunction "2D_4") (pintype "input"))
      (node (ref "IC4") (pin "4") (pinfunction "2D_4") (pintype "input"))
      (node (ref "IC5") (pin "4") (pinfunction "2D_4") (pintype "input"))
      (node (ref "IC6") (pin "4") (pinfunction "2D_4") (pintype "input"))
      (node (ref "IC7") (pin "4") (pinfunction "2D_4") (pintype "input"))
      (node (ref "IC8") (pin "4") (pinfunction "2D_4") (pintype "input"))
    )
    (net (code "157") (name "PIA-A2") (class "Default")
      (node (ref "CORE-IO") (pin "3") (pinfunction "3_3") (pintype "passive"))
      (node (ref "IC1") (pin "7") (pinfunction "3D_7") (pintype "input"))
      (node (ref "IC11") (pin "6") (pinfunction "3Q_6") (pintype "tri_state"))
      (node (ref "IC12") (pin "6") (pinfunction "3Q_6") (pintype "tri_state"))
      (node (ref "IC13") (pin "6") (pinfunction "3Q_6") (pintype "tri_state"))
      (node (ref "IC14") (pin "6") (pinfunction "3Q_6") (pintype "tri_state"))
      (node (ref "IC15") (pin "6") (pinfunction "3Q_6") (pintype "tri_state"))
      (node (ref "IC16") (pin "6") (pinfunction "3Q_6") (pintype "tri_state"))
      (node (ref "IC17") (pin "6") (pinfunction "3Q_6") (pintype "tri_state"))
      (node (ref "IC18") (pin "6") (pinfunction "3Q_6") (pintype "tri_state"))
      (node (ref "IC2") (pin "7") (pinfunction "3D_7") (pintype "input"))
      (node (ref "IC3") (pin "7") (pinfunction "3D_7") (pintype "input"))
      (node (ref "IC4") (pin "7") (pinfunction "3D_7") (pintype "input"))
      (node (ref "IC5") (pin "7") (pinfunction "3D_7") (pintype "input"))
      (node (ref "IC6") (pin "7") (pinfunction "3D_7") (pintype "input"))
      (node (ref "IC7") (pin "7") (pinfunction "3D_7") (pintype "input"))
      (node (ref "IC8") (pin "7") (pinfunction "3D_7") (pintype "input"))
    )
    (net (code "158") (name "PIA-A3") (class "Default")
      (node (ref "CORE-IO") (pin "4") (pinfunction "4_4") (pintype "passive"))
      (node (ref "IC1") (pin "8") (pinfunction "4D_8") (pintype "input"))
      (node (ref "IC11") (pin "9") (pinfunction "4Q_9") (pintype "tri_state"))
      (node (ref "IC12") (pin "9") (pinfunction "4Q_9") (pintype "tri_state"))
      (node (ref "IC13") (pin "9") (pinfunction "4Q_9") (pintype "tri_state"))
      (node (ref "IC14") (pin "9") (pinfunction "4Q_9") (pintype "tri_state"))
      (node (ref "IC15") (pin "9") (pinfunction "4Q_9") (pintype "tri_state"))
      (node (ref "IC16") (pin "9") (pinfunction "4Q_9") (pintype "tri_state"))
      (node (ref "IC17") (pin "9") (pinfunction "4Q_9") (pintype "tri_state"))
      (node (ref "IC18") (pin "9") (pinfunction "4Q_9") (pintype "tri_state"))
      (node (ref "IC2") (pin "8") (pinfunction "4D_8") (pintype "input"))
      (node (ref "IC3") (pin "8") (pinfunction "4D_8") (pintype "input"))
      (node (ref "IC4") (pin "8") (pinfunction "4D_8") (pintype "input"))
      (node (ref "IC5") (pin "8") (pinfunction "4D_8") (pintype "input"))
      (node (ref "IC6") (pin "8") (pinfunction "4D_8") (pintype "input"))
      (node (ref "IC7") (pin "8") (pinfunction "4D_8") (pintype "input"))
      (node (ref "IC8") (pin "8") (pinfunction "4D_8") (pintype "input"))
    )
    (net (code "159") (name "PIA-A4") (class "Default")
      (node (ref "CORE-IO") (pin "5") (pinfunction "5_5") (pintype "passive"))
      (node (ref "IC1") (pin "13") (pinfunction "5D_13") (pintype "input"))
      (node (ref "IC11") (pin "12") (pinfunction "5Q_12") (pintype "tri_state"))
      (node (ref "IC12") (pin "12") (pinfunction "5Q_12") (pintype "tri_state"))
      (node (ref "IC13") (pin "12") (pinfunction "5Q_12") (pintype "tri_state"))
      (node (ref "IC14") (pin "12") (pinfunction "5Q_12") (pintype "tri_state"))
      (node (ref "IC15") (pin "12") (pinfunction "5Q_12") (pintype "tri_state"))
      (node (ref "IC16") (pin "12") (pinfunction "5Q_12") (pintype "tri_state"))
      (node (ref "IC17") (pin "12") (pinfunction "5Q_12") (pintype "tri_state"))
      (node (ref "IC18") (pin "12") (pinfunction "5Q_12") (pintype "tri_state"))
      (node (ref "IC2") (pin "13") (pinfunction "5D_13") (pintype "input"))
      (node (ref "IC3") (pin "13") (pinfunction "5D_13") (pintype "input"))
      (node (ref "IC4") (pin "13") (pinfunction "5D_13") (pintype "input"))
      (node (ref "IC5") (pin "13") (pinfunction "5D_13") (pintype "input"))
      (node (ref "IC6") (pin "13") (pinfunction "5D_13") (pintype "input"))
      (node (ref "IC7") (pin "13") (pinfunction "5D_13") (pintype "input"))
      (node (ref "IC8") (pin "13") (pinfunction "5D_13") (pintype "input"))
    )
    (net (code "160") (name "PIA-A5") (class "Default")
      (node (ref "CORE-IO") (pin "6") (pinfunction "6_6") (pintype "passive"))
      (node (ref "IC1") (pin "14") (pinfunction "6D_14") (pintype "input"))
      (node (ref "IC11") (pin "15") (pinfunction "6Q_15") (pintype "tri_state"))
      (node (ref "IC12") (pin "15") (pinfunction "6Q_15") (pintype "tri_state"))
      (node (ref "IC13") (pin "15") (pinfunction "6Q_15") (pintype "tri_state"))
      (node (ref "IC14") (pin "15") (pinfunction "6Q_15") (pintype "tri_state"))
      (node (ref "IC15") (pin "15") (pinfunction "6Q_15") (pintype "tri_state"))
      (node (ref "IC16") (pin "15") (pinfunction "6Q_15") (pintype "tri_state"))
      (node (ref "IC17") (pin "15") (pinfunction "6Q_15") (pintype "tri_state"))
      (node (ref "IC18") (pin "15") (pinfunction "6Q_15") (pintype "tri_state"))
      (node (ref "IC2") (pin "14") (pinfunction "6D_14") (pintype "input"))
      (node (ref "IC3") (pin "14") (pinfunction "6D_14") (pintype "input"))
      (node (ref "IC4") (pin "14") (pinfunction "6D_14") (pintype "input"))
      (node (ref "IC5") (pin "14") (pinfunction "6D_14") (pintype "input"))
      (node (ref "IC6") (pin "14") (pinfunction "6D_14") (pintype "input"))
      (node (ref "IC7") (pin "14") (pinfunction "6D_14") (pintype "input"))
      (node (ref "IC8") (pin "14") (pinfunction "6D_14") (pintype "input"))
    )
    (net (code "161") (name "PIA-A6") (class "Default")
      (node (ref "CORE-IO") (pin "7") (pinfunction "7_7") (pintype "passive"))
      (node (ref "IC1") (pin "17") (pinfunction "7D_17") (pintype "input"))
      (node (ref "IC11") (pin "16") (pinfunction "7Q_16") (pintype "tri_state"))
      (node (ref "IC12") (pin "16") (pinfunction "7Q_16") (pintype "tri_state"))
      (node (ref "IC13") (pin "16") (pinfunction "7Q_16") (pintype "tri_state"))
      (node (ref "IC14") (pin "16") (pinfunction "7Q_16") (pintype "tri_state"))
      (node (ref "IC15") (pin "16") (pinfunction "7Q_16") (pintype "tri_state"))
      (node (ref "IC16") (pin "16") (pinfunction "7Q_16") (pintype "tri_state"))
      (node (ref "IC17") (pin "16") (pinfunction "7Q_16") (pintype "tri_state"))
      (node (ref "IC18") (pin "16") (pinfunction "7Q_16") (pintype "tri_state"))
      (node (ref "IC2") (pin "17") (pinfunction "7D_17") (pintype "input"))
      (node (ref "IC3") (pin "17") (pinfunction "7D_17") (pintype "input"))
      (node (ref "IC4") (pin "17") (pinfunction "7D_17") (pintype "input"))
      (node (ref "IC5") (pin "17") (pinfunction "7D_17") (pintype "input"))
      (node (ref "IC6") (pin "17") (pinfunction "7D_17") (pintype "input"))
      (node (ref "IC7") (pin "17") (pinfunction "7D_17") (pintype "input"))
      (node (ref "IC8") (pin "17") (pinfunction "7D_17") (pintype "input"))
    )
    (net (code "162") (name "PIA-A7") (class "Default")
      (node (ref "CORE-IO") (pin "8") (pinfunction "8_8") (pintype "passive"))
      (node (ref "IC1") (pin "18") (pinfunction "8D_18") (pintype "input"))
      (node (ref "IC11") (pin "19") (pinfunction "8Q_19") (pintype "tri_state"))
      (node (ref "IC12") (pin "19") (pinfunction "8Q_19") (pintype "tri_state"))
      (node (ref "IC13") (pin "19") (pinfunction "8Q_19") (pintype "tri_state"))
      (node (ref "IC14") (pin "19") (pinfunction "8Q_19") (pintype "tri_state"))
      (node (ref "IC15") (pin "19") (pinfunction "8Q_19") (pintype "tri_state"))
      (node (ref "IC16") (pin "19") (pinfunction "8Q_19") (pintype "tri_state"))
      (node (ref "IC17") (pin "19") (pinfunction "8Q_19") (pintype "tri_state"))
      (node (ref "IC18") (pin "19") (pinfunction "8Q_19") (pintype "tri_state"))
      (node (ref "IC2") (pin "18") (pinfunction "8D_18") (pintype "input"))
      (node (ref "IC3") (pin "18") (pinfunction "8D_18") (pintype "input"))
      (node (ref "IC4") (pin "18") (pinfunction "8D_18") (pintype "input"))
      (node (ref "IC5") (pin "18") (pinfunction "8D_18") (pintype "input"))
      (node (ref "IC6") (pin "18") (pinfunction "8D_18") (pintype "input"))
      (node (ref "IC7") (pin "18") (pinfunction "8D_18") (pintype "input"))
      (node (ref "IC8") (pin "18") (pinfunction "8D_18") (pintype "input"))
    )
    (net (code "163") (name "PIA-B0") (class "Default")
      (node (ref "CORE-IO") (pin "13") (pinfunction "13_13") (pintype "passive"))
      (node (ref "IC10") (pin "1") (pinfunction "A_1") (pintype "input"))
      (node (ref "IC9") (pin "1") (pinfunction "A_1") (pintype "input"))
    )
    (net (code "164") (name "PIA-B1") (class "Default")
      (node (ref "CORE-IO") (pin "14") (pinfunction "14_14") (pintype "passive"))
      (node (ref "IC10") (pin "2") (pinfunction "B_2") (pintype "input"))
      (node (ref "IC9") (pin "2") (pinfunction "B_2") (pintype "input"))
    )
    (net (code "165") (name "PIA-B2") (class "Default")
      (node (ref "CORE-IO") (pin "15") (pinfunction "15_15") (pintype "passive"))
      (node (ref "IC10") (pin "3") (pinfunction "C_3") (pintype "input"))
      (node (ref "IC9") (pin "3") (pinfunction "C_3") (pintype "input"))
    )
    (net (code "166") (name "PIA-B3") (class "Default")
      (node (ref "CORE-IO") (pin "16") (pinfunction "16_16") (pintype "passive"))
      (node (ref "IC19") (pin "1") (pinfunction "A_1") (pintype "input"))
    )
    (net (code "167") (name "PIA-B4") (class "Default")
      (node (ref "CORE-IO") (pin "17") (pinfunction "17_17") (pintype "passive"))
      (node (ref "IC19") (pin "2") (pinfunction "B_2") (pintype "input"))
    )
    (net (code "168") (name "PIA-B5") (class "Default")
      (node (ref "CORE-IO") (pin "18") (pinfunction "18_18") (pintype "passive"))
      (node (ref "IC19") (pin "3") (pinfunction "C_3") (pintype "input"))
    )
    (net (code "169") (name "PIA-B6") (class "Default")
      (node (ref "CORE-IO") (pin "19") (pinfunction "19_19") (pintype "passive"))
      (node (ref "IC10") (pin "6") (pinfunction "G1_6") (pintype "input"))
      (node (ref "IC9") (pin "4") (pinfunction "G2A_4") (pintype "input"))
    )
    (net (code "170") (name "PIA-B7") (class "Default")
      (node (ref "CORE-IO") (pin "20") (pinfunction "20_20") (pintype "passive"))
      (node (ref "DEVSEL") (pin "2") (pinfunction "2_2") (pintype "passive"))
      (node (ref "IC19") (pin "5") (pinfunction "G2B_5") (pintype "input"))
    )
    (net (code "171") (name "VCC") (class "Default")
      (node (ref "BYP1") (pin "1") (pinfunction "1_1") (pintype "passive"))
      (node (ref "BYP10") (pin "1") (pinfunction "1_1") (pintype "passive"))
      (node (ref "BYP11") (pin "1") (pinfunction "1_1") (pintype "passive"))
      (node (ref "BYP12") (pin "1") (pinfunction "1_1") (pintype "passive"))
      (node (ref "BYP13") (pin "1") (pinfunction "1_1") (pintype "passive"))
      (node (ref "BYP14") (pin "1") (pinfunction "1_1") (pintype "passive"))
      (node (ref "BYP15") (pin "1") (pinfunction "1_1") (pintype "passive"))
      (node (ref "BYP16") (pin "1") (pinfunction "1_1") (pintype "passive"))
      (node (ref "BYP17") (pin "1") (pinfunction "1_1") (pintype "passive"))
      (node (ref "BYP18") (pin "1") (pinfunction "1_1") (pintype "passive"))
      (node (ref "BYP19") (pin "1") (pinfunction "1_1") (pintype "passive"))
      (node (ref "BYP2") (pin "1") (pinfunction "1_1") (pintype "passive"))
      (node (ref "BYP20") (pin "1") (pinfunction "1_1") (pintype "passive"))
      (node (ref "BYP3") (pin "1") (pinfunction "1_1") (pintype "passive"))
      (node (ref "BYP4") (pin "1") (pinfunction "1_1") (pintype "passive"))
      (node (ref "BYP5") (pin "1") (pinfunction "1_1") (pintype "passive"))
      (node (ref "BYP6") (pin "1") (pinfunction "1_1") (pintype "passive"))
      (node (ref "BYP7") (pin "1") (pinfunction "1_1") (pintype "passive"))
      (node (ref "BYP8") (pin "1") (pinfunction "1_1") (pintype "passive"))
      (node (ref "BYP9") (pin "1") (pinfunction "1_1") (pintype "passive"))
      (node (ref "CORE-IO") (pin "12") (pinfunction "12_12") (pintype "passive"))
      (node (ref "CORE-IO") (pin "9") (pinfunction "9_9") (pintype "passive"))
      (node (ref "IC11") (pin "11") (pinfunction "ENC_11") (pintype "input"))
      (node (ref "IC12") (pin "11") (pinfunction "ENC_11") (pintype "input"))
      (node (ref "IC13") (pin "11") (pinfunction "ENC_11") (pintype "input"))
      (node (ref "IC14") (pin "11") (pinfunction "ENC_11") (pintype "input"))
      (node (ref "IC15") (pin "11") (pinfunction "ENC_11") (pintype "input"))
      (node (ref "IC16") (pin "11") (pinfunction "ENC_11") (pintype "input"))
      (node (ref "IC17") (pin "11") (pinfunction "ENC_11") (pintype "input"))
      (node (ref "IC18") (pin "11") (pinfunction "ENC_11") (pintype "input"))
      (node (ref "IC19") (pin "6") (pinfunction "G1_6") (pintype "input"))
      (node (ref "IC9") (pin "6") (pinfunction "G1_6") (pintype "input"))
      (node (ref "JP2") (pin "2") (pinfunction "2_2") (pintype "passive"))
    )
  )
)
